# Schematic.net
KiCad netlist of a schematic drawn in EasyEDA
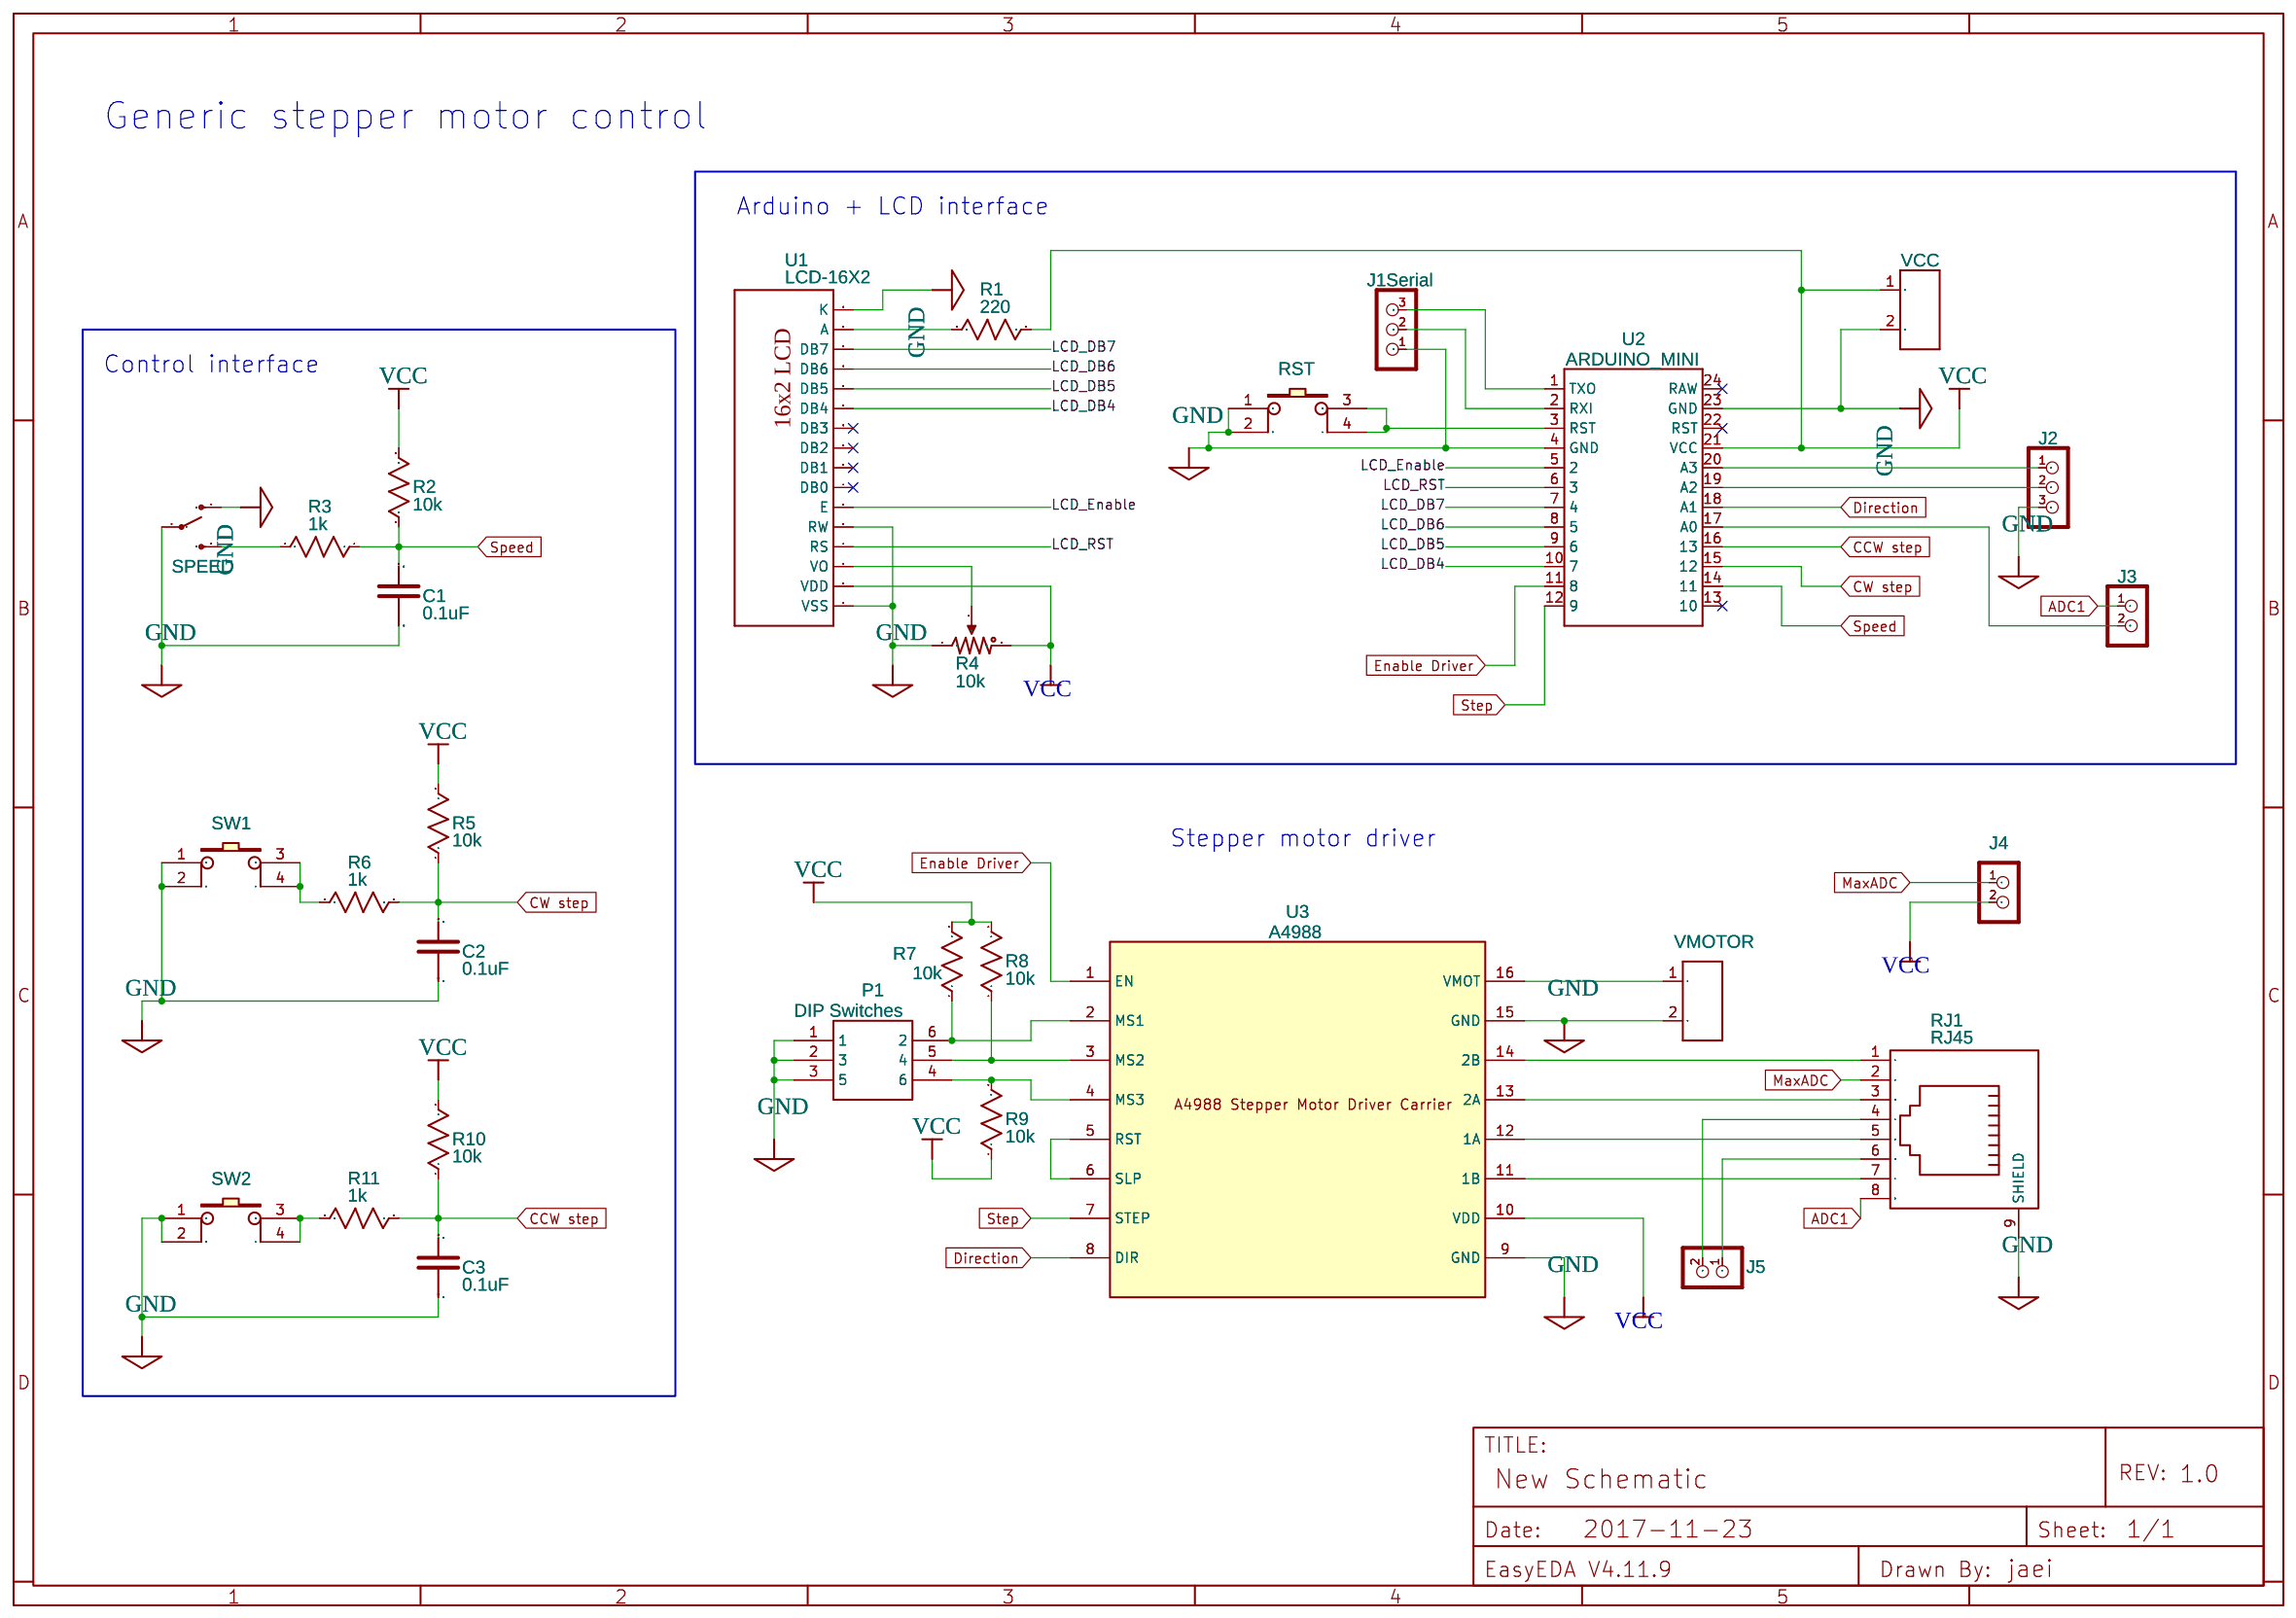
[diagram p0: schematic sheet]

(export (version "E")
  (design (tool "Eeschema 10.0.6"))
  (components
    (comp (ref "C1")
      (value "0.1uF")
      (fields (field (name "BOM_Manufacturer Part") "?"))
      (libsource (lib "") (part "Unknown_195_290"))
    )
    (comp (ref "C2")
      (value "0.1uF")
      (fields (field (name "BOM_Manufacturer Part") "?"))
      (libsource (lib "") (part "Unknown_215_470"))
    )
    (comp (ref "C3")
      (value "0.1uF")
      (fields (field (name "BOM_Manufacturer Part") "?"))
      (libsource (lib "") (part "Unknown_215_630"))
    )
    (comp (ref "J1-SERIAL")
      (value "J1Serial")
      (fields (field (name "BOM_Manufacturer Part") "?"))
      (libsource (lib "") (part "Unknown_705_160"))
    )
    (comp (ref "J2")
      (value "CON_HEADER_1X03-PTH")
      (fields (field (name "BOM_Manufacturer Part") "?"))
      (libsource (lib "") (part "Unknown_1025_240"))
    )
    (comp (ref "J3")
      (value "CON_HEADER_1X02-PTH")
      (fields (field (name "BOM_Manufacturer Part") "?"))
      (libsource (lib "") (part "Unknown_1065_300"))
    )
    (comp (ref "J4")
      (value "CON_HEADER_1X02-PTH")
      (fields (field (name "BOM_Manufacturer Part") "?"))
      (libsource (lib "") (part "Unknown_1000_440"))
    )
    (comp (ref "J5")
      (value "CON_HEADER_1X02-PTH")
      (fields (field (name "BOM_Manufacturer Part") "?"))
      (libsource (lib "") (part "Unknown_865_630"))
    )
    (comp (ref "P1")
      (value "DIP Switches")
      (fields
        (field (name "BOM_Manufacturer Part") "HDR-IDC-2.54-2X3P")
        (field (name "BOM_Supplier Part") "C11214")
      )
      (libsource (lib "") (part "Unknown_435_550"))
    )
    (comp (ref "R1")
      (value "220")
      (fields (field (name "BOM_Manufacturer Part") "?"))
      (libsource (lib "") (part "Resistor_2"))
    )
    (comp (ref "R2")
      (value "10k")
      (fields (field (name "BOM_Manufacturer Part") "?"))
      (libsource (lib "") (part "Resistor"))
    )
    (comp (ref "R3")
      (value "1k")
      (fields (field (name "BOM_Manufacturer Part") "?"))
      (libsource (lib "") (part "Resistor_2"))
    )
    (comp (ref "R4")
      (value "10k")
      (fields (field (name "BOM_Manufacturer Part") "?"))
      (libsource (lib "") (part "Potentiometer"))
    )
    (comp (ref "R5")
      (value "10k")
      (fields (field (name "BOM_Manufacturer Part") "?"))
      (libsource (lib "") (part "Resistor"))
    )
    (comp (ref "R6")
      (value "1k")
      (fields (field (name "BOM_Manufacturer Part") "?"))
      (libsource (lib "") (part "Resistor_1"))
    )
    (comp (ref "R7")
      (value "10k")
      (fields (field (name "BOM_Manufacturer Part") "?"))
      (libsource (lib "") (part "Resistor"))
    )
    (comp (ref "R8")
      (value "10k")
      (fields (field (name "BOM_Manufacturer Part") "?"))
      (libsource (lib "") (part "Resistor"))
    )
    (comp (ref "R9")
      (value "10k")
      (fields (field (name "BOM_Manufacturer Part") "?"))
      (libsource (lib "") (part "Resistor"))
    )
    (comp (ref "R10")
      (value "10k")
      (fields (field (name "BOM_Manufacturer Part") "?"))
      (libsource (lib "") (part "Resistor"))
    )
    (comp (ref "R11")
      (value "1k")
      (fields (field (name "BOM_Manufacturer Part") "?"))
      (libsource (lib "") (part "Resistor_2"))
    )
    (comp (ref "RJ1")
      (value "RJ45")
      (fields (field (name "BOM_Supplier Part") "C36373"))
      (libsource (lib "") (part "Unknown_1025_570"))
    )
    (comp (ref "RST")
      (value "SWITCH-6x6x5_TH")
      (fields (field (name "BOM_Supplier Part") "C69330"))
      (libsource (lib "") (part "Unknown_655_210"))
    )
    (comp (ref "SPEED")
      (value "SWITCH-SPDT")
      (fields (field (name "BOM_Manufacturer Part") "?"))
      (libsource (lib "") (part "Unknown_85_260"))
    )
    (comp (ref "SW1")
      (value "SWITCH-6x6x5_TH")
      (fields (field (name "BOM_Supplier Part") "C69330"))
      (libsource (lib "") (part "Unknown_115_440"))
    )
    (comp (ref "SW2")
      (value "SWITCH-6x6x5_TH")
      (fields (field (name "BOM_Supplier Part") "C69330"))
      (libsource (lib "") (part "Unknown_115_620"))
    )
    (comp (ref "U1")
      (value "LCD-16X2")
      (fields (field (name "BOM_Manufacturer Part") "?"))
      (libsource (lib "") (part "Unknown_385_220"))
    )
    (comp (ref "U2")
      (value "ARDUINO_MINI")
      (fields (field (name "BOM_Manufacturer Part") "?"))
      (libsource (lib "") (part "Unknown_815_240"))
    )
    (comp (ref "U3")
      (value "A4988")
      (fields (field (name "BOM_Manufacturer Part") "?"))
      (libsource (lib "") (part "Unknown_555_650"))
    )
    (comp (ref "VCC") (value "GS009S-2P-2") (libsource (lib "") (part "Unknown_965_150")))
    (comp (ref "VMOTOR") (value "GS009S-2P-2") (libsource (lib "") (part "Unknown_855_500")))
  )
  (nets
    (net (code "1") (name "/LCD_DB4") (class "Default")
      (node (ref "U1") (pin "11") (pinfunction "DB4_11") (pintype "unspecified"))
      (node (ref "U2") (pin "10") (pinfunction "7_10") (pintype "unspecified"))
    )
    (net (code "2") (name "/LCD_DB5") (class "Default")
      (node (ref "U1") (pin "12") (pinfunction "DB5_12") (pintype "unspecified"))
      (node (ref "U2") (pin "9") (pinfunction "6_9") (pintype "unspecified"))
    )
    (net (code "3") (name "/LCD_DB6") (class "Default")
      (node (ref "U1") (pin "13") (pinfunction "DB6_13") (pintype "unspecified"))
      (node (ref "U2") (pin "8") (pinfunction "5_8") (pintype "unspecified"))
    )
    (net (code "4") (name "/LCD_DB7") (class "Default")
      (node (ref "U1") (pin "14") (pinfunction "DB7_14") (pintype "unspecified"))
      (node (ref "U2") (pin "7") (pinfunction "4_7") (pintype "unspecified"))
    )
    (net (code "5") (name "/LCD_Enable") (class "Default")
      (node (ref "U1") (pin "6") (pinfunction "E_6") (pintype "input"))
      (node (ref "U2") (pin "5") (pinfunction "2_5") (pintype "unspecified"))
    )
    (net (code "6") (name "/LCD_RST") (class "Default")
      (node (ref "U1") (pin "4") (pinfunction "RS_4") (pintype "input"))
      (node (ref "U2") (pin "6") (pinfunction "3_6") (pintype "unspecified"))
    )
    (net (code "7") (name "ADC1") (class "Default")
      (node (ref "J3") (pin "1") (pinfunction "1_1") (pintype "unspecified"))
      (node (ref "RJ1") (pin "8") (pinfunction "8_8") (pintype "unspecified"))
    )
    (net (code "8") (name "CCW step") (class "Default")
      (node (ref "C3") (pin "P$1") (pinfunction "P$1_P$1") (pintype "unspecified"))
      (node (ref "R10") (pin "1") (pinfunction "1_1") (pintype "unspecified"))
      (node (ref "R11") (pin "1") (pinfunction "1_1") (pintype "unspecified"))
      (node (ref "U2") (pin "16") (pinfunction "13_16") (pintype "unspecified"))
    )
    (net (code "9") (name "CW step") (class "Default")
      (node (ref "C2") (pin "P$1") (pinfunction "P$1_P$1") (pintype "unspecified"))
      (node (ref "R5") (pin "1") (pinfunction "1_1") (pintype "unspecified"))
      (node (ref "R6") (pin "2") (pinfunction "2_2") (pintype "unspecified"))
      (node (ref "U2") (pin "15") (pinfunction "12_15") (pintype "unspecified"))
    )
    (net (code "10") (name "Direction") (class "Default")
      (node (ref "U2") (pin "18") (pinfunction "A1_18") (pintype "unspecified"))
      (node (ref "U3") (pin "8") (pinfunction "DIR_8") (pintype "unspecified"))
    )
    (net (code "11") (name "Enable Driver") (class "Default")
      (node (ref "U2") (pin "11") (pinfunction "8_11") (pintype "unspecified"))
      (node (ref "U3") (pin "1") (pinfunction "EN_1") (pintype "unspecified"))
    )
    (net (code "12") (name "GND") (class "Default")
      (node (ref "C1") (pin "P$2") (pinfunction "P$2_P$2") (pintype "unspecified"))
      (node (ref "C2") (pin "P$2") (pinfunction "P$2_P$2") (pintype "unspecified"))
      (node (ref "C3") (pin "P$2") (pinfunction "P$2_P$2") (pintype "unspecified"))
      (node (ref "J1-SERIAL") (pin "1") (pinfunction "1_1") (pintype "unspecified"))
      (node (ref "J2") (pin "3") (pinfunction "3_3") (pintype "unspecified"))
      (node (ref "P1") (pin "1") (pinfunction "1_1") (pintype "unspecified"))
      (node (ref "P1") (pin "2") (pinfunction "3_2") (pintype "unspecified"))
      (node (ref "P1") (pin "3") (pinfunction "5_3") (pintype "unspecified"))
      (node (ref "R4") (pin "1") (pinfunction "1_1") (pintype "unspecified"))
      (node (ref "RJ1") (pin "9") (pinfunction "SHIELD_9") (pintype "unspecified"))
      (node (ref "RST") (pin "1") (pinfunction "1_1") (pintype "input"))
      (node (ref "RST") (pin "2") (pinfunction "2_2") (pintype "input"))
      (node (ref "SPEED") (pin "1") (pinfunction "O_1") (pintype "unspecified"))
      (node (ref "SPEED") (pin "2") (pinfunction "P_2") (pintype "unspecified"))
      (node (ref "SW1") (pin "1") (pinfunction "1_1") (pintype "input"))
      (node (ref "SW1") (pin "2") (pinfunction "2_2") (pintype "input"))
      (node (ref "SW2") (pin "1") (pinfunction "1_1") (pintype "input"))
      (node (ref "SW2") (pin "2") (pinfunction "2_2") (pintype "input"))
      (node (ref "U1") (pin "1") (pinfunction "VSS_1") (pintype "passive"))
      (node (ref "U1") (pin "16") (pinfunction "K_16") (pintype "passive"))
      (node (ref "U1") (pin "5") (pinfunction "RW_5") (pintype "input"))
      (node (ref "U2") (pin "23") (pinfunction "GND_23") (pintype "unspecified"))
      (node (ref "U2") (pin "4") (pinfunction "GND_4") (pintype "unspecified"))
      (node (ref "U3") (pin "15") (pinfunction "GND_15") (pintype "unspecified"))
      (node (ref "U3") (pin "9") (pinfunction "GND_9") (pintype "unspecified"))
      (node (ref "VCC") (pin "2") (pinfunction "2_2") (pintype "unspecified"))
      (node (ref "VMOTOR") (pin "2") (pinfunction "2_2") (pintype "unspecified"))
    )
    (net (code "13") (name "MaxADC") (class "Default")
      (node (ref "J4") (pin "1") (pinfunction "1_1") (pintype "unspecified"))
      (node (ref "RJ1") (pin "2") (pinfunction "2_2") (pintype "unspecified"))
    )
    (net (code "14") (name "Net-(J5-Pad1)") (class "Default")
      (node (ref "J5") (pin "1") (pinfunction "1_1") (pintype "unspecified"))
      (node (ref "RJ1") (pin "6") (pinfunction "6_6") (pintype "unspecified"))
    )
    (net (code "15") (name "Net-(J5-Pad2)") (class "Default")
      (node (ref "J5") (pin "2") (pinfunction "2_2") (pintype "unspecified"))
      (node (ref "RJ1") (pin "4") (pinfunction "4_4") (pintype "unspecified"))
    )
    (net (code "16") (name "Net-(P1-2)") (class "Default")
      (node (ref "P1") (pin "6") (pinfunction "2_6") (pintype "unspecified"))
      (node (ref "R7") (pin "1") (pinfunction "1_1") (pintype "unspecified"))
      (node (ref "U3") (pin "2") (pinfunction "MS1_2") (pintype "unspecified"))
    )
    (net (code "17") (name "Net-(P1-4)") (class "Default")
      (node (ref "P1") (pin "5") (pinfunction "4_5") (pintype "unspecified"))
      (node (ref "R8") (pin "1") (pinfunction "1_1") (pintype "unspecified"))
      (node (ref "U3") (pin "3") (pinfunction "MS2_3") (pintype "unspecified"))
    )
    (net (code "18") (name "Net-(P1-6)") (class "Default")
      (node (ref "P1") (pin "4") (pinfunction "6_4") (pintype "unspecified"))
      (node (ref "R9") (pin "2") (pinfunction "2_2") (pintype "unspecified"))
      (node (ref "U3") (pin "4") (pinfunction "MS3_4") (pintype "unspecified"))
    )
    (net (code "19") (name "Net-(R4-3)") (class "Default")
      (node (ref "R4") (pin "2") (pinfunction "3_2") (pintype "unspecified"))
      (node (ref "U1") (pin "3") (pinfunction "VO_3") (pintype "unspecified"))
    )
    (net (code "20") (name "Net-(R6-Pad1)") (class "Default")
      (node (ref "R6") (pin "1") (pinfunction "1_1") (pintype "unspecified"))
      (node (ref "SW1") (pin "3") (pinfunction "3_3") (pintype "input"))
      (node (ref "SW1") (pin "4") (pinfunction "4_4") (pintype "input"))
    )
    (net (code "21") (name "Net-(R11-Pad2)") (class "Default")
      (node (ref "R11") (pin "2") (pinfunction "2_2") (pintype "unspecified"))
      (node (ref "SW2") (pin "3") (pinfunction "3_3") (pintype "input"))
      (node (ref "SW2") (pin "4") (pinfunction "4_4") (pintype "input"))
    )
    (net (code "22") (name "Net-(RST-Pad3)") (class "Default")
      (node (ref "RST") (pin "3") (pinfunction "3_3") (pintype "input"))
      (node (ref "RST") (pin "4") (pinfunction "4_4") (pintype "input"))
      (node (ref "U2") (pin "3") (pinfunction "RST_3") (pintype "unspecified"))
    )
    (net (code "23") (name "Net-(SPEED-S)") (class "Default")
      (node (ref "R3") (pin "2") (pinfunction "2_2") (pintype "unspecified"))
      (node (ref "SPEED") (pin "3") (pinfunction "S_3") (pintype "unspecified"))
    )
    (net (code "24") (name "Net-(U1-A)") (class "Default")
      (node (ref "R1") (pin "2") (pinfunction "2_2") (pintype "unspecified"))
      (node (ref "U1") (pin "15") (pinfunction "A_15") (pintype "passive"))
    )
    (net (code "25") (name "Net-(U2-A0)") (class "Default")
      (node (ref "J3") (pin "2") (pinfunction "2_2") (pintype "unspecified"))
      (node (ref "U2") (pin "17") (pinfunction "A0_17") (pintype "unspecified"))
    )
    (net (code "26") (name "Net-(U2-A2)") (class "Default")
      (node (ref "J2") (pin "2") (pinfunction "2_2") (pintype "unspecified"))
      (node (ref "U2") (pin "19") (pinfunction "A2_19") (pintype "unspecified"))
    )
    (net (code "27") (name "Net-(U2-A3)") (class "Default")
      (node (ref "J2") (pin "1") (pinfunction "1_1") (pintype "unspecified"))
      (node (ref "U2") (pin "20") (pinfunction "A3_20") (pintype "unspecified"))
    )
    (net (code "28") (name "Net-(U2-RXI)") (class "Default")
      (node (ref "J1-SERIAL") (pin "2") (pinfunction "2_2") (pintype "unspecified"))
      (node (ref "U2") (pin "2") (pinfunction "RXI_2") (pintype "unspecified"))
    )
    (net (code "29") (name "Net-(U2-TXO)") (class "Default")
      (node (ref "J1-SERIAL") (pin "3") (pinfunction "3_3") (pintype "unspecified"))
      (node (ref "U2") (pin "1") (pinfunction "TXO_1") (pintype "unspecified"))
    )
    (net (code "30") (name "Net-(U3-1A)") (class "Default")
      (node (ref "RJ1") (pin "5") (pinfunction "5_5") (pintype "unspecified"))
      (node (ref "U3") (pin "12") (pinfunction "1A_12") (pintype "unspecified"))
    )
    (net (code "31") (name "Net-(U3-1B)") (class "Default")
      (node (ref "RJ1") (pin "7") (pinfunction "7_7") (pintype "unspecified"))
      (node (ref "U3") (pin "11") (pinfunction "1B_11") (pintype "unspecified"))
    )
    (net (code "32") (name "Net-(U3-2A)") (class "Default")
      (node (ref "RJ1") (pin "3") (pinfunction "3_3") (pintype "unspecified"))
      (node (ref "U3") (pin "13") (pinfunction "2A_13") (pintype "unspecified"))
    )
    (net (code "33") (name "Net-(U3-2B)") (class "Default")
      (node (ref "RJ1") (pin "1") (pinfunction "1_1") (pintype "unspecified"))
      (node (ref "U3") (pin "14") (pinfunction "2B_14") (pintype "unspecified"))
    )
    (net (code "34") (name "Net-(U3-RST)") (class "Default")
      (node (ref "U3") (pin "5") (pinfunction "RST_5") (pintype "unspecified"))
      (node (ref "U3") (pin "6") (pinfunction "SLP_6") (pintype "unspecified"))
    )
    (net (code "35") (name "Net-(U3-VMOT)") (class "Default")
      (node (ref "U3") (pin "16") (pinfunction "VMOT_16") (pintype "unspecified"))
      (node (ref "VMOTOR") (pin "1") (pinfunction "1_1") (pintype "unspecified"))
    )
    (net (code "36") (name "Speed") (class "Default")
      (node (ref "C1") (pin "P$1") (pinfunction "P$1_P$1") (pintype "unspecified"))
      (node (ref "R2") (pin "1") (pinfunction "1_1") (pintype "unspecified"))
      (node (ref "R3") (pin "1") (pinfunction "1_1") (pintype "unspecified"))
      (node (ref "U2") (pin "14") (pinfunction "11_14") (pintype "unspecified"))
    )
    (net (code "37") (name "Step") (class "Default")
      (node (ref "U2") (pin "12") (pinfunction "9_12") (pintype "unspecified"))
      (node (ref "U3") (pin "7") (pinfunction "STEP_7") (pintype "unspecified"))
    )
    (net (code "38") (name "VCC") (class "Default")
      (node (ref "J4") (pin "2") (pinfunction "2_2") (pintype "unspecified"))
      (node (ref "R1") (pin "1") (pinfunction "1_1") (pintype "unspecified"))
      (node (ref "R10") (pin "2") (pinfunction "2_2") (pintype "unspecified"))
      (node (ref "R2") (pin "2") (pinfunction "2_2") (pintype "unspecified"))
      (node (ref "R4") (pin "3") (pinfunction "2_3") (pintype "unspecified"))
      (node (ref "R5") (pin "2") (pinfunction "2_2") (pintype "unspecified"))
      (node (ref "R7") (pin "2") (pinfunction "2_2") (pintype "unspecified"))
      (node (ref "R8") (pin "2") (pinfunction "2_2") (pintype "unspecified"))
      (node (ref "R9") (pin "1") (pinfunction "1_1") (pintype "unspecified"))
      (node (ref "U1") (pin "2") (pinfunction "VDD_2") (pintype "passive"))
      (node (ref "U2") (pin "21") (pinfunction "VCC_21") (pintype "unspecified"))
      (node (ref "U3") (pin "10") (pinfunction "VDD_10") (pintype "unspecified"))
      (node (ref "VCC") (pin "1") (pinfunction "1_1") (pintype "unspecified"))
    )
    (net (code "39") (name "unconnected-(U1-DB0-Pad7)") (class "Default")
      (node (ref "U1") (pin "7") (pinfunction "DB0_7") (pintype "unspecified+no_connect"))
    )
    (net (code "40") (name "unconnected-(U1-DB1-Pad8)") (class "Default")
      (node (ref "U1") (pin "8") (pinfunction "DB1_8") (pintype "unspecified+no_connect"))
    )
    (net (code "41") (name "unconnected-(U1-DB2-Pad9)") (class "Default")
      (node (ref "U1") (pin "9") (pinfunction "DB2_9") (pintype "unspecified+no_connect"))
    )
    (net (code "42") (name "unconnected-(U1-DB3-Pad10)") (class "Default")
      (node (ref "U1") (pin "10") (pinfunction "DB3_10") (pintype "unspecified+no_connect"))
    )
    (net (code "43") (name "unconnected-(U2-10-Pad13)") (class "Default")
      (node (ref "U2") (pin "13") (pinfunction "10_13") (pintype "unspecified+no_connect"))
    )
    (net (code "44") (name "unconnected-(U2-RAW-Pad24)") (class "Default")
      (node (ref "U2") (pin "24") (pinfunction "RAW_24") (pintype "unspecified+no_connect"))
    )
    (net (code "45") (name "unconnected-(U2-RST-Pad22)") (class "Default")
      (node (ref "U2") (pin "22") (pinfunction "RST_22") (pintype "unspecified+no_connect"))
    )
  )
)
